# CTRL_Board.net
KiCad netlist of a schematic drawn in Altium Designer
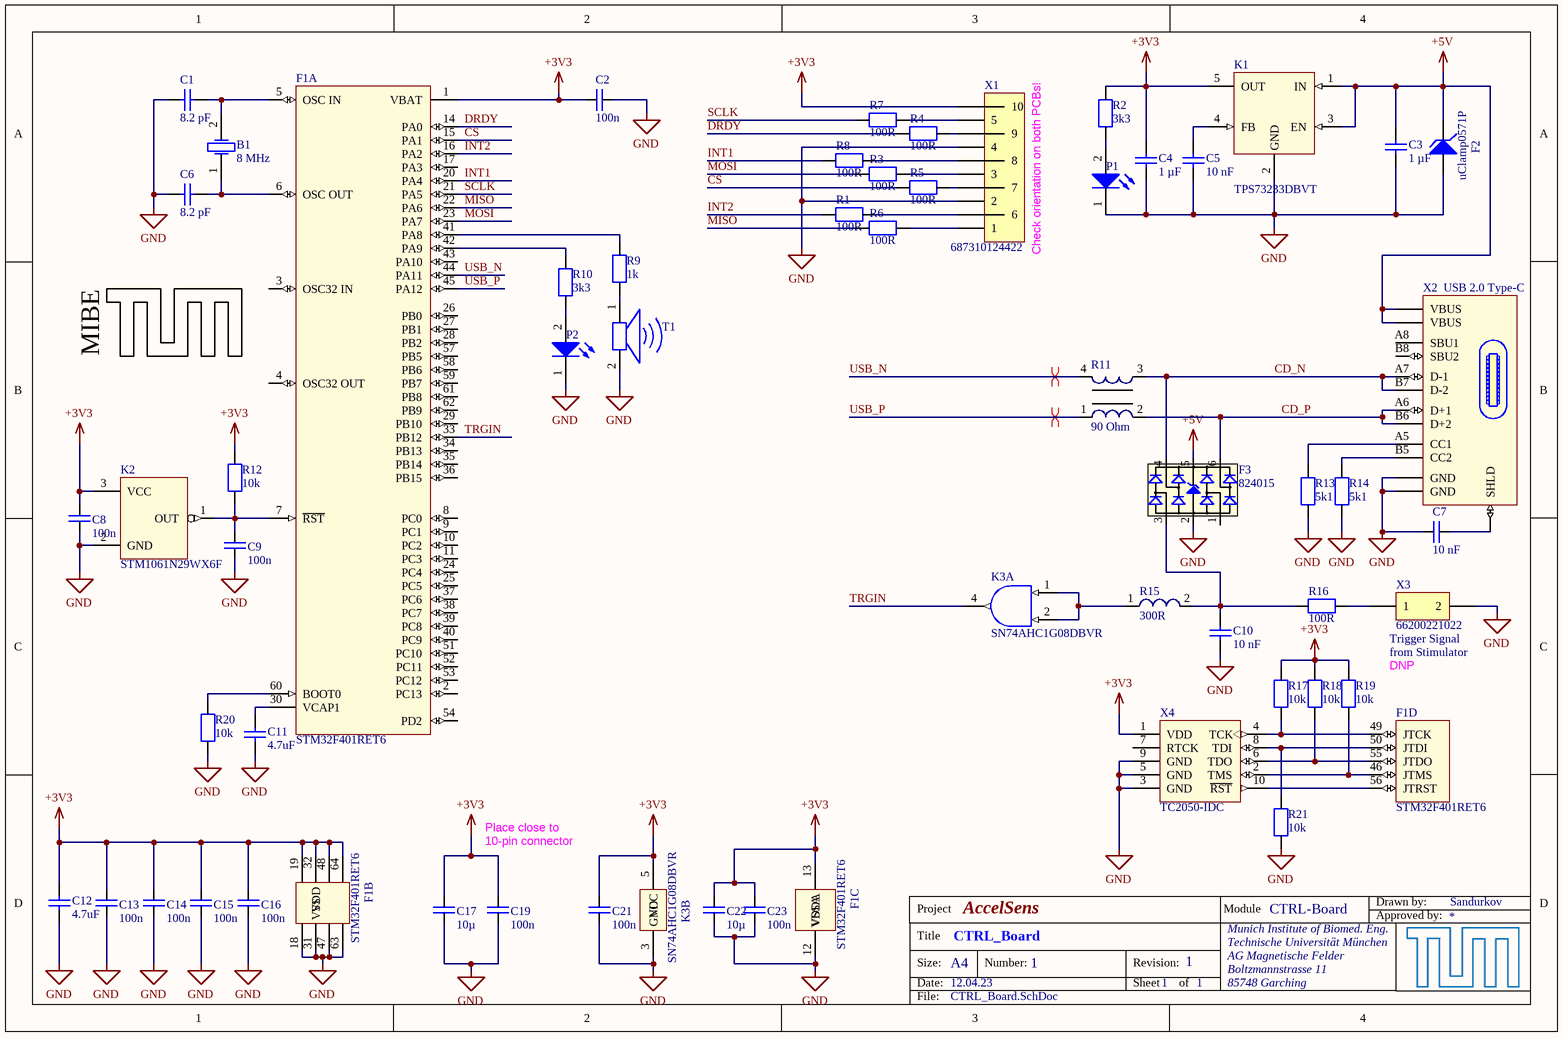
[diagram p0: CTRL_Board.SchDoc]

(export (version "E")
  (design (tool "Eeschema 10.0.6"))
  (components
    (comp (ref "*1")
      (value "TUM & MIBE Logo")
      (footprint "TUM & MIBE Logo")
      (libsource (lib "Mechanical") (part "TUM & MIBE Logo"))
    )
    (comp (ref "B1")
      (value "8 MHz")
      (footprint "DFN190P320X100-2N")
      (description "Crystal, 8 MHz, 8 pF, NX3225GD")
      (libsource (lib "Crystals") (part "NX3225GD-8MHZ-STD-CRA-3"))
    )
    (comp (ref "C1")
      (value "8.2 pF")
      (footprint "CAPC1608X09N")
      (description "8.2 pF, 50 V, 5%, C0G, 0805")
      (libsource (lib "Capacitors") (part "C0603C829C5GACTU"))
    )
    (comp (ref "C2")
      (value "100n")
      (footprint "CAPC1608X08N")
      (description "100n, 0603, X7R, 10%, 50 V")
      (fields (field (name "MANUFACTURER") "Kemet") (field (name "TOLERANCE") "10%"))
      (libsource (lib "Capacitors") (part "C0603C104K5RACTU"))
    )
    (comp (ref "C3")
      (value "1 µF")
      (footprint "CAPC2012X14N")
      (description "1 µF, 25 V, 10%, X7R, 0805")
      (libsource (lib "Capacitors") (part "C0805C105K3RACTU"))
    )
    (comp (ref "C4")
      (value "1 µF")
      (footprint "CAPC2012X14N")
      (description "1 µF, 25 V, 10%, X7R, 0805")
      (libsource (lib "Capacitors") (part "C0805C105K3RACTU"))
    )
    (comp (ref "C5")
      (value "10 nF")
      (footprint "CAPC2012X09N")
      (description "10 nF, 50 V, 10%, X7R, 0805")
      (libsource (lib "Capacitors") (part "C0805C103K5RACTU"))
    )
    (comp (ref "C6")
      (value "8.2 pF")
      (footprint "CAPC1608X09N")
      (description "8.2 pF, 50 V, 5%, C0G, 0805")
      (libsource (lib "Capacitors") (part "C0603C829C5GACTU"))
    )
    (comp (ref "C7")
      (value "10 nF")
      (footprint "0603 (1608x90N), h = 0.9 mm")
      (description "10 nF, 50 V, 10%, X7R, 0603")
      (fields
        (field (name "MANUFACTURER") "Yageo")
        (field (name "MANUFACTURER PART NUMBER") "CC0603KRX7R9BB103")
      )
      (libsource (lib "Capacitors_MIBE") (part "CC0603KRX7R9BB103"))
    )
    (comp (ref "C8")
      (value "100n")
      (footprint "CAPC1608X08N")
      (description "100n, 0603, X7R, 10%, 50 V")
      (fields (field (name "MANUFACTURER") "Kemet") (field (name "TOLERANCE") "10%"))
      (libsource (lib "Capacitors") (part "C0603C104K5RACTU"))
    )
    (comp (ref "C9")
      (value "100n")
      (footprint "CAPC1608X08N")
      (description "100n, 0603, X7R, 10%, 50 V")
      (fields (field (name "MANUFACTURER") "Kemet") (field (name "TOLERANCE") "10%"))
      (libsource (lib "Capacitors") (part "C0603C104K5RACTU"))
    )
    (comp (ref "C10")
      (value "10 nF")
      (footprint "CAPC2012X09N")
      (description "10 nF, 50 V, 10%, X7R, 0805")
      (libsource (lib "Capacitors") (part "C0805C103K5RACTU"))
    )
    (comp (ref "C11")
      (value "4.7uF")
      (footprint "CAPC2012X09N")
      (description "4.7 µF, ± 10%, X5R, 16 V, 0805")
      (libsource (lib "Capacitors") (part "C0805C475K4PACTU"))
    )
    (comp (ref "C12")
      (value "4.7uF")
      (footprint "CAPC2012X09N")
      (description "4.7 µF, ± 10%, X5R, 16 V, 0805")
      (libsource (lib "Capacitors") (part "C0805C475K4PACTU"))
    )
    (comp (ref "C13")
      (value "100n")
      (footprint "CAPC1608X08N")
      (description "100n, 0603, X7R, 10%, 50 V")
      (fields (field (name "MANUFACTURER") "Kemet") (field (name "TOLERANCE") "10%"))
      (libsource (lib "Capacitors") (part "C0603C104K5RACTU"))
    )
    (comp (ref "C14")
      (value "100n")
      (footprint "CAPC1608X08N")
      (description "100n, 0603, X7R, 10%, 50 V")
      (fields (field (name "MANUFACTURER") "Kemet") (field (name "TOLERANCE") "10%"))
      (libsource (lib "Capacitors") (part "C0603C104K5RACTU"))
    )
    (comp (ref "C15")
      (value "100n")
      (footprint "CAPC1608X08N")
      (description "100n, 0603, X7R, 10%, 50 V")
      (fields (field (name "MANUFACTURER") "Kemet") (field (name "TOLERANCE") "10%"))
      (libsource (lib "Capacitors") (part "C0603C104K5RACTU"))
    )
    (comp (ref "C16")
      (value "100n")
      (footprint "CAPC1608X08N")
      (description "100n, 0603, X7R, 10%, 50 V")
      (fields (field (name "MANUFACTURER") "Kemet") (field (name "TOLERANCE") "10%"))
      (libsource (lib "Capacitors") (part "C0603C104K5RACTU"))
    )
    (comp (ref "C17")
      (value "10µ")
      (footprint "CAPC2012X14N")
      (description "10µ, 0805, X5R, 10%, 16 V")
      (fields (field (name "MANUFACTURER") "Kemet") (field (name "TOLERANCE") "10%"))
      (libsource (lib "Capacitors") (part "C0805C106K4PACTU"))
    )
    (comp (ref "C19")
      (value "100n")
      (footprint "CAPC1608X08N")
      (description "100n, 0603, X7R, 10%, 50 V")
      (fields (field (name "MANUFACTURER") "Kemet") (field (name "TOLERANCE") "10%"))
      (libsource (lib "Capacitors") (part "C0603C104K5RACTU"))
    )
    (comp (ref "C21")
      (value "100n")
      (footprint "CAPC1608X08N")
      (description "100n, 0603, X7R, 10%, 50 V")
      (fields (field (name "MANUFACTURER") "Kemet") (field (name "TOLERANCE") "10%"))
      (libsource (lib "Capacitors") (part "C0603C104K5RACTU"))
    )
    (comp (ref "C22")
      (value "10µ")
      (footprint "CAPC2012X14N")
      (description "10µ, 0805, X5R, 10%, 16 V")
      (fields (field (name "MANUFACTURER") "Kemet") (field (name "TOLERANCE") "10%"))
      (libsource (lib "Capacitors") (part "C0805C106K4PACTU"))
    )
    (comp (ref "C23")
      (value "100n")
      (footprint "CAPC1608X08N")
      (description "100n, 0603, X7R, 10%, 50 V")
      (fields (field (name "MANUFACTURER") "Kemet") (field (name "TOLERANCE") "10%"))
      (libsource (lib "Capacitors") (part "C0603C104K5RACTU"))
    )
    (comp (ref "F1")
      (value "STM32F401RET6")
      (footprint "LQFP-64")
      (description "M4, 512 kB, 84 MHz")
      (fields (field (name "MANUFACTURER") "STMicroelectronics"))
      (libsource (lib "Microcontroller_MIBE") (part "STM32F401RET6"))
    )
    (comp (ref "F2")
      (value "uClamp0571P")
      (footprint "DFN110P160X55-2N")
      (description "TVS DIODE 5V 15V SGP1610N2")
      (fields
        (field (name "MANUFACTURER") "Semtech")
        (field (name "MANUFACTURER PART NUMBER") "UCLAMP0571P.TNT")
      )
      (libsource (lib "Diodes") (part "UCLAMP0571P.TNT"))
    )
    (comp (ref "F3")
      (value "824015")
      (footprint "SOT23_6L")
      (description "TVS Diode WE-TVS-HS, VRWM=5V")
      (fields
        (field (name "MANUFACTURER") "Würth Elektronik eiSos GmbH")
        (field (name "CREATED BY") "Christin Zierenner")
      )
      (libsource (lib "Diodes") (part "WE-TVS-HS, 824015"))
    )
    (comp (ref "K1")
      (value "TPS73233DBVT")
      (footprint "SOT95P280X145-5N")
      (description "Low Noise, Positive Output LDO, 250 mA, 3.3V")
      (fields (field (name "PUBLISHER") "Stephan Huber"))
      (libsource (lib "Regulators") (part "TPS73233DBVT"))
    )
    (comp (ref "K2")
      (value "STM1061N29WX6F")
      (footprint "SOT95P237X112-3N")
      (description "Low Power Voltage Detector, Open Drain, 2,9 V Threshold, SOT23-3")
      (libsource (lib "Supervisors") (part "STM1061N29WX6F"))
    )
    (comp (ref "K3")
      (value "SN74AHC1G08DBVR")
      (footprint "SOT95P280X145-5N")
      (description "CMOS Single AND-Gate, AHC, 2 V - 5.5 V, 8 mA, Ultra High Speed")
      (libsource (lib "Logic") (part "SN74AHC1G08DBVR"))
    )
    (comp (ref "P1")
      (value "green")
      (footprint "WL-SMCW_0603")
      (description "WL-SMCW LED, green, 30 mA, 2 V, 570 nmr, 0603, Bright Green,  140°")
      (fields (field (name "PART NUMBER") "150060VS75000") (field (name "PUBLISHER") "Wurth Elektronik"))
      (libsource (lib "Opto") (part "150060VS75000"))
    )
    (comp (ref "P2")
      (value "green")
      (footprint "WL-SMCW_0603")
      (description "WL-SMCW LED, green, 30 mA, 2 V, 570 nmr, 0603, Bright Green,  140°")
      (fields (field (name "PART NUMBER") "150060VS75000") (field (name "PUBLISHER") "Wurth Elektronik"))
      (libsource (lib "Opto") (part "150060VS75000"))
    )
    (comp (ref "R1")
      (value "100R")
      (footprint "RESC1608X05N")
      (description "100R, 0603, 0.25 W, 1%, 75 V, pulse proof")
      (fields (field (name "TOLERANCE") "1%") (field (name "MANUFACTURER") "Vishay"))
      (libsource (lib "Resistors") (part "CRCW0603100RFKEAHP"))
    )
    (comp (ref "R2")
      (value "3k3")
      (footprint "RESC1608X05N")
      (description "3k3, 0603, 0.1 W, 1%, 75 V")
      (fields (field (name "TOLERANCE") "1%") (field (name "MANUFACTURER") "Vishay"))
      (libsource (lib "") (part "CRCW06033K30FKEA_1"))
    )
    (comp (ref "R3")
      (value "100R")
      (footprint "RESC1608X05N")
      (description "100R, 0603, 0.25 W, 1%, 75 V, pulse proof")
      (fields (field (name "TOLERANCE") "1%") (field (name "MANUFACTURER") "Vishay"))
      (libsource (lib "Resistors") (part "CRCW0603100RFKEAHP"))
    )
    (comp (ref "R4")
      (value "100R")
      (footprint "RESC1608X05N")
      (description "100R, 0603, 0.25 W, 1%, 75 V, pulse proof")
      (fields (field (name "TOLERANCE") "1%") (field (name "MANUFACTURER") "Vishay"))
      (libsource (lib "Resistors") (part "CRCW0603100RFKEAHP"))
    )
    (comp (ref "R5")
      (value "100R")
      (footprint "RESC1608X05N")
      (description "100R, 0603, 0.25 W, 1%, 75 V, pulse proof")
      (fields (field (name "TOLERANCE") "1%") (field (name "MANUFACTURER") "Vishay"))
      (libsource (lib "Resistors") (part "CRCW0603100RFKEAHP"))
    )
    (comp (ref "R6")
      (value "100R")
      (footprint "RESC1608X05N")
      (description "100R, 0603, 0.25 W, 1%, 75 V, pulse proof")
      (fields (field (name "TOLERANCE") "1%") (field (name "MANUFACTURER") "Vishay"))
      (libsource (lib "Resistors") (part "CRCW0603100RFKEAHP"))
    )
    (comp (ref "R7")
      (value "100R")
      (footprint "RESC1608X05N")
      (description "100R, 0603, 0.25 W, 1%, 75 V, pulse proof")
      (fields (field (name "TOLERANCE") "1%") (field (name "MANUFACTURER") "Vishay"))
      (libsource (lib "Resistors") (part "CRCW0603100RFKEAHP"))
    )
    (comp (ref "R8")
      (value "100R")
      (footprint "RESC1608X05N")
      (description "100R, 0603, 0.25 W, 1%, 75 V, pulse proof")
      (fields (field (name "TOLERANCE") "1%") (field (name "MANUFACTURER") "Vishay"))
      (libsource (lib "Resistors") (part "CRCW0603100RFKEAHP"))
    )
    (comp (ref "R9")
      (value "1k")
      (footprint "RESC1608X05N")
      (description "1k, 0603, 0.1 W, 1%, 75 V")
      (fields (field (name "TOLERANCE") "1%") (field (name "MANUFACTURER") "Vishay"))
      (libsource (lib "Resistors") (part "CRCW06031K00FKEA"))
    )
    (comp (ref "R10")
      (value "3k3")
      (footprint "RESC1608X05N")
      (description "3k3, 0603, 0.1 W, 1%, 75 V")
      (fields (field (name "TOLERANCE") "1%") (field (name "MANUFACTURER") "Vishay"))
      (libsource (lib "Resistors") (part "CRCW06033K30FKEA"))
    )
    (comp (ref "R11")
      (value "90 Ohm")
      (footprint "WE-CNSW, 1206")
      (description "SMD Common Mode Noise Suppressor WE-CNSW,  Z= 90 Ohm")
      (fields
        (field (name "PARTNO") "744232090")
        (field (name "MANUFACTURER") "Würth Elektronik eiSos GmbH")
        (field (name "CREATED BY") "Christin Zierenner")
      )
      (libsource (lib "Inductors") (part "WE-CNSW 1206, 744232090"))
    )
    (comp (ref "R12")
      (value "10k")
      (footprint "RESC1608X05N")
      (description "10k, 0603, 0.1 W, 1%, 75 V")
      (fields (field (name "TOLERANCE") "1%") (field (name "MANUFACTURER") "Vishay"))
      (libsource (lib "Resistors") (part "CRCW060310K0FKEA"))
    )
    (comp (ref "R13")
      (value "5k1")
      (footprint "RES0603")
      (description "5k1, 0.1 W, 1%, 75 V, 0603")
      (fields
        (field (name "MANUFACTURER") "Vishay")
        (field (name "MANUFACTURER PART NUMBER") "CRCW06035K10FKEA")
      )
      (libsource (lib "Resistors_MIBE") (part "CRCW06035K10FKEA"))
    )
    (comp (ref "R14")
      (value "5k1")
      (footprint "RES0603")
      (description "5k1, 0.1 W, 1%, 75 V, 0603")
      (fields
        (field (name "MANUFACTURER") "Vishay")
        (field (name "MANUFACTURER PART NUMBER") "CRCW06035K10FKEA")
      )
      (libsource (lib "Resistors_MIBE") (part "CRCW06035K10FKEA"))
    )
    (comp (ref "R15")
      (value "300R")
      (footprint "0603 (WE-CBF)")
      (description "300R / 100 MHz, 2 A, 0R15, WE-CBF")
      (fields
        (field (name "MANUFACTURER") "Wurth Electronics")
        (field (name "MANUFACTURER PART NUMBER") "742792641")
      )
      (libsource (lib "Inductors_MIBE") (part "742792641"))
    )
    (comp (ref "R16")
      (value "100R")
      (footprint "RESC1608X05N")
      (description "100R, 0603, 0.25 W, 1%, 75 V, pulse proof")
      (fields (field (name "TOLERANCE") "1%") (field (name "MANUFACTURER") "Vishay"))
      (libsource (lib "") (part "CRCW0603100RFKEAHP_1"))
    )
    (comp (ref "R17")
      (value "10k")
      (footprint "RESC1608X05N")
      (description "10k, 0603, 0.1 W, 0.1%, 75 V")
      (fields (field (name "TOLERANCE") "0.1%") (field (name "MANUFACTURER") "Panasonic"))
      (libsource (lib "Resistors") (part "ERA3AEB103V"))
    )
    (comp (ref "R18")
      (value "10k")
      (footprint "RESC1608X05N")
      (description "10k, 0603, 0.1 W, 0.1%, 75 V")
      (fields (field (name "TOLERANCE") "0.1%") (field (name "MANUFACTURER") "Panasonic"))
      (libsource (lib "Resistors") (part "ERA3AEB103V"))
    )
    (comp (ref "R19")
      (value "10k")
      (footprint "RESC1608X05N")
      (description "10k, 0603, 0.1 W, 0.1%, 75 V")
      (fields (field (name "TOLERANCE") "0.1%") (field (name "MANUFACTURER") "Panasonic"))
      (libsource (lib "Resistors") (part "ERA3AEB103V"))
    )
    (comp (ref "R20")
      (value "10k")
      (footprint "RESC1608X05N")
      (description "10k, 0603, 0.1 W, 1%, 75 V")
      (fields (field (name "TOLERANCE") "1%") (field (name "MANUFACTURER") "Vishay"))
      (libsource (lib "Resistors") (part "CRCW060310K0FKEA"))
    )
    (comp (ref "R21")
      (value "10k")
      (footprint "RESC1608X05N")
      (description "10k, 0603, 0.1 W, 0.1%, 75 V")
      (fields (field (name "TOLERANCE") "0.1%") (field (name "MANUFACTURER") "Panasonic"))
      (libsource (lib "Resistors") (part "ERA3AEB103V"))
    )
    (comp (ref "T1")
      (value "Summer")
      (footprint "PKLCS1212E4001-R1")
      (description "SUMMER, SMD, 4KHZ EXTERN BESCHALTEN")
      (libsource (lib "Electromechanical") (part "PKLCS1212E4001-R1"))
    )
    (comp (ref "X1")
      (value "687310124422")
      (footprint "687310124422")
      (description "Ffc / Fpc Board Connector, Vertical, Surface Mount, Receptacle, 10, 0.5 Mm Rohs Compliant: Yes")
      (fields (field (name "MANUFACTURER") "Wurth Electronics"))
      (libsource (lib "Connectors_MIBE") (part "687310124422"))
    )
    (comp (ref "X2")
      (value "USB 2.0 Type-C")
      (footprint "629722000214")
      (description "USB 2.0 Type C")
      (fields
        (field (name "MANUFACTURER") "Wurth Electronics")
        (field (name "MANUFACTURER PART NUMBER") "629722000214")
      )
      (libsource (lib "Connectors_MIBE") (part "629722000214"))
    )
    (comp (ref "X3")
      (value "66200221022")
      (footprint "66200221022")
      (description "WR-MPC3 3.00 mm Male Dual Row Angled Header with Plastic Pegs")
      (fields
        (field (name "MANUFACTURER") "Würth Elektronik eiSos GmbH")
        (field (name "CREATED BY") "Karrer Zheng")
      )
      (libsource (lib "Connectors") (part "WE-3.00 mm Micro Power Connector 66200221022"))
    )
    (comp (ref "X4")
      (value "TC2050-IDC")
      (footprint "TC2050-IDC")
      (description "JTAG - Adapter Cbl Plug Of Nails 10PIN")
      (fields (field (name "MANUFACTURER") "Tag-Connect"))
      (libsource (lib "Connectors_MIBE") (part "TC2050-IDC"))
    )
  )
  (nets
    (net (code "1") (name "+3V3") (class "Default")
      (node (ref "C12") (pin "1") (pinfunction "1_1") (pintype "passive"))
      (node (ref "C13") (pin "1") (pinfunction "1_1") (pintype "passive"))
      (node (ref "C14") (pin "1") (pinfunction "1_1") (pintype "passive"))
      (node (ref "C15") (pin "1") (pinfunction "1_1") (pintype "passive"))
      (node (ref "C16") (pin "1") (pinfunction "1_1") (pintype "passive"))
      (node (ref "C17") (pin "1") (pinfunction "1_1") (pintype "passive"))
      (node (ref "C19") (pin "1") (pinfunction "1_1") (pintype "passive"))
      (node (ref "C2") (pin "1") (pinfunction "1_1") (pintype "passive"))
      (node (ref "C21") (pin "1") (pinfunction "1_1") (pintype "passive"))
      (node (ref "C22") (pin "1") (pinfunction "1_1") (pintype "passive"))
      (node (ref "C23") (pin "1") (pinfunction "1_1") (pintype "passive"))
      (node (ref "C4") (pin "1") (pinfunction "1_1") (pintype "passive"))
      (node (ref "C8") (pin "1") (pinfunction "1_1") (pintype "passive"))
      (node (ref "F1") (pin "1") (pinfunction "VBAT_1") (pintype "power_in"))
      (node (ref "F1") (pin "13") (pinfunction "VDDA_13") (pintype "power_in"))
      (node (ref "F1") (pin "19") (pinfunction "VDD_19") (pintype "power_in"))
      (node (ref "F1") (pin "32") (pinfunction "VDD_32") (pintype "power_in"))
      (node (ref "F1") (pin "48") (pinfunction "VDD_48") (pintype "power_in"))
      (node (ref "F1") (pin "64") (pinfunction "VDD_64") (pintype "power_in"))
      (node (ref "K1") (pin "5") (pinfunction "OUT_5") (pintype "power_in"))
      (node (ref "K2") (pin "3") (pinfunction "VCC_3") (pintype "power_in"))
      (node (ref "K3") (pin "5") (pinfunction "VCC_5") (pintype "power_in"))
      (node (ref "R12") (pin "1") (pinfunction "1_1") (pintype "passive"))
      (node (ref "R17") (pin "1") (pinfunction "1_1") (pintype "passive"))
      (node (ref "R18") (pin "1") (pinfunction "1_1") (pintype "passive"))
      (node (ref "R19") (pin "1") (pinfunction "1_1") (pintype "passive"))
      (node (ref "R2") (pin "1") (pinfunction "1_1") (pintype "passive"))
      (node (ref "X1") (pin "10") (pinfunction "10_10") (pintype "passive"))
      (node (ref "X4") (pin "1") (pinfunction "VDD_1") (pintype "power_in"))
    )
    (net (code "2") (name "+5V") (class "Default")
      (node (ref "C3") (pin "1") (pinfunction "1_1") (pintype "passive"))
      (node (ref "F2") (pin "1") (pinfunction "C_1") (pintype "passive"))
      (node (ref "F3") (pin "5") (pinfunction "VDD_5") (pintype "passive"))
      (node (ref "K1") (pin "1") (pinfunction "IN_1") (pintype "input"))
      (node (ref "K1") (pin "3") (pinfunction "EN_3") (pintype "input"))
      (node (ref "X2") (pin "VBUS") (pinfunction "VBUS_VBUS") (pintype "power_in"))
    )
    (net (code "3") (name "/CD_N") (class "Default")
      (node (ref "F3") (pin "4") (pinfunction "I/O3_4") (pintype "passive"))
      (node (ref "R11") (pin "3") (pinfunction "3_3") (pintype "passive"))
      (node (ref "X2") (pin "A7") (pinfunction "D-1_A7") (pintype "bidirectional"))
      (node (ref "X2") (pin "B7") (pinfunction "D-2_B7") (pintype "passive"))
    )
    (net (code "4") (name "/CD_P") (class "Default")
      (node (ref "F3") (pin "6") (pinfunction "I/O4_6") (pintype "passive"))
      (node (ref "R11") (pin "2") (pinfunction "2_2") (pintype "passive"))
      (node (ref "X2") (pin "A6") (pinfunction "D+1_A6") (pintype "bidirectional"))
      (node (ref "X2") (pin "B6") (pinfunction "D+2_B6") (pintype "power_in"))
    )
    (net (code "5") (name "/CS") (class "Default")
      (node (ref "F1") (pin "15") (pinfunction "PA1_15") (pintype "bidirectional"))
      (node (ref "R5") (pin "2") (pinfunction "2_2") (pintype "passive"))
    )
    (net (code "6") (name "/DRDY") (class "Default")
      (node (ref "F1") (pin "14") (pinfunction "PA0_14") (pintype "bidirectional"))
      (node (ref "R4") (pin "2") (pinfunction "2_2") (pintype "passive"))
    )
    (net (code "7") (name "/INT1") (class "Default")
      (node (ref "F1") (pin "20") (pinfunction "PA4_20") (pintype "bidirectional"))
      (node (ref "R8") (pin "2") (pinfunction "2_2") (pintype "passive"))
    )
    (net (code "8") (name "/INT2") (class "Default")
      (node (ref "F1") (pin "16") (pinfunction "PA2_16") (pintype "bidirectional"))
      (node (ref "R1") (pin "2") (pinfunction "2_2") (pintype "passive"))
    )
    (net (code "9") (name "/MISO") (class "Default")
      (node (ref "F1") (pin "22") (pinfunction "PA6_22") (pintype "bidirectional"))
      (node (ref "R6") (pin "2") (pinfunction "2_2") (pintype "passive"))
    )
    (net (code "10") (name "/MOSI") (class "Default")
      (node (ref "F1") (pin "23") (pinfunction "PA7_23") (pintype "bidirectional"))
      (node (ref "R3") (pin "2") (pinfunction "2_2") (pintype "passive"))
    )
    (net (code "11") (name "/SCLK") (class "Default")
      (node (ref "F1") (pin "21") (pinfunction "PA5_21") (pintype "bidirectional"))
      (node (ref "R7") (pin "2") (pinfunction "2_2") (pintype "passive"))
    )
    (net (code "12") (name "/TRGIN") (class "Default")
      (node (ref "F1") (pin "33") (pinfunction "PB12_33") (pintype "bidirectional"))
      (node (ref "K3") (pin "4") (pinfunction "Y_4") (pintype "output"))
    )
    (net (code "13") (name "/USB_N") (class "Default")
      (node (ref "F1") (pin "44") (pinfunction "PA11_44") (pintype "bidirectional"))
      (node (ref "R11") (pin "4") (pinfunction "4_4") (pintype "passive"))
    )
    (net (code "14") (name "/USB_P") (class "Default")
      (node (ref "F1") (pin "45") (pinfunction "PA12_45") (pintype "bidirectional"))
      (node (ref "R11") (pin "1") (pinfunction "1_1") (pintype "passive"))
    )
    (net (code "15") (name "GND") (class "Default")
      (node (ref "C1") (pin "1") (pinfunction "1_1") (pintype "passive"))
      (node (ref "C10") (pin "2") (pinfunction "2_2") (pintype "passive"))
      (node (ref "C11") (pin "2") (pinfunction "2_2") (pintype "passive"))
      (node (ref "C12") (pin "2") (pinfunction "2_2") (pintype "passive"))
      (node (ref "C13") (pin "2") (pinfunction "2_2") (pintype "passive"))
      (node (ref "C14") (pin "2") (pinfunction "2_2") (pintype "passive"))
      (node (ref "C15") (pin "2") (pinfunction "2_2") (pintype "passive"))
      (node (ref "C16") (pin "2") (pinfunction "2_2") (pintype "passive"))
      (node (ref "C17") (pin "2") (pinfunction "2_2") (pintype "passive"))
      (node (ref "C19") (pin "2") (pinfunction "2_2") (pintype "passive"))
      (node (ref "C2") (pin "2") (pinfunction "2_2") (pintype "passive"))
      (node (ref "C21") (pin "2") (pinfunction "2_2") (pintype "passive"))
      (node (ref "C22") (pin "2") (pinfunction "2_2") (pintype "passive"))
      (node (ref "C23") (pin "2") (pinfunction "2_2") (pintype "passive"))
      (node (ref "C3") (pin "2") (pinfunction "2_2") (pintype "passive"))
      (node (ref "C4") (pin "2") (pinfunction "2_2") (pintype "passive"))
      (node (ref "C5") (pin "2") (pinfunction "2_2") (pintype "passive"))
      (node (ref "C6") (pin "1") (pinfunction "1_1") (pintype "passive"))
      (node (ref "C7") (pin "1") (pinfunction "1_1") (pintype "passive"))
      (node (ref "C8") (pin "2") (pinfunction "2_2") (pintype "passive"))
      (node (ref "C9") (pin "2") (pinfunction "2_2") (pintype "passive"))
      (node (ref "F1") (pin "12") (pinfunction "VSSA_12") (pintype "power_in"))
      (node (ref "F1") (pin "18") (pinfunction "VSS_18") (pintype "power_in"))
      (node (ref "F1") (pin "31") (pinfunction "VSS_31") (pintype "power_in"))
      (node (ref "F1") (pin "47") (pinfunction "VSS_47") (pintype "power_in"))
      (node (ref "F1") (pin "63") (pinfunction "VSS_63") (pintype "power_in"))
      (node (ref "F2") (pin "2") (pinfunction "A_2") (pintype "passive"))
      (node (ref "F3") (pin "2") (pinfunction "GND_2") (pintype "passive"))
      (node (ref "K1") (pin "2") (pinfunction "GND_2") (pintype "power_in"))
      (node (ref "K2") (pin "2") (pinfunction "GND_2") (pintype "power_in"))
      (node (ref "K3") (pin "3") (pinfunction "GND_3") (pintype "power_in"))
      (node (ref "P1") (pin "1") (pinfunction "K_1") (pintype "passive"))
      (node (ref "P2") (pin "1") (pinfunction "K_1") (pintype "passive"))
      (node (ref "R13") (pin "2") (pinfunction "2_2") (pintype "passive"))
      (node (ref "R14") (pin "2") (pinfunction "2_2") (pintype "passive"))
      (node (ref "R20") (pin "2") (pinfunction "2_2") (pintype "passive"))
      (node (ref "R21") (pin "2") (pinfunction "2_2") (pintype "passive"))
      (node (ref "T1") (pin "2") (pinfunction "2_2") (pintype "passive"))
      (node (ref "X1") (pin "2") (pinfunction "2_2") (pintype "passive"))
      (node (ref "X1") (pin "4") (pinfunction "4_4") (pintype "passive"))
      (node (ref "X2") (pin "GND") (pinfunction "GND_GND") (pintype "power_in"))
      (node (ref "X3") (pin "2") (pinfunction "2_2") (pintype "passive"))
      (node (ref "X4") (pin "3") (pinfunction "GND_3") (pintype "power_in"))
      (node (ref "X4") (pin "5") (pinfunction "GND_5") (pintype "power_in"))
      (node (ref "X4") (pin "9") (pinfunction "GND_9") (pintype "power_in"))
    )
    (net (code "16") (name "Net-(F1A-BOOT0)") (class "Default")
      (node (ref "F1") (pin "60") (pinfunction "BOOT0_60") (pintype "input"))
      (node (ref "R20") (pin "1") (pinfunction "1_1") (pintype "passive"))
    )
    (net (code "17") (name "Net-(F1A-OSC_IN)") (class "Default")
      (node (ref "B1") (pin "2") (pinfunction "2_2") (pintype "passive"))
      (node (ref "C1") (pin "2") (pinfunction "2_2") (pintype "passive"))
      (node (ref "F1") (pin "5") (pinfunction "OSC_IN_5") (pintype "bidirectional"))
    )
    (net (code "18") (name "Net-(F1A-OSC_OUT)") (class "Default")
      (node (ref "B1") (pin "1") (pinfunction "1_1") (pintype "passive"))
      (node (ref "C6") (pin "2") (pinfunction "2_2") (pintype "passive"))
      (node (ref "F1") (pin "6") (pinfunction "OSC_OUT_6") (pintype "bidirectional"))
    )
    (net (code "19") (name "Net-(F1A-PA8)") (class "Default")
      (node (ref "F1") (pin "41") (pinfunction "PA8_41") (pintype "bidirectional"))
      (node (ref "R9") (pin "1") (pinfunction "1_1") (pintype "passive"))
    )
    (net (code "20") (name "Net-(F1A-PA9)") (class "Default")
      (node (ref "F1") (pin "42") (pinfunction "PA9_42") (pintype "bidirectional"))
      (node (ref "R10") (pin "2") (pinfunction "2_2") (pintype "passive"))
    )
    (net (code "21") (name "Net-(F1A-VCAP1)") (class "Default")
      (node (ref "C11") (pin "1") (pinfunction "1_1") (pintype "passive"))
      (node (ref "F1") (pin "30") (pinfunction "VCAP1_30") (pintype "power_in"))
    )
    (net (code "22") (name "Net-(F1A-~{RST})") (class "Default")
      (node (ref "C9") (pin "1") (pinfunction "1_1") (pintype "passive"))
      (node (ref "F1") (pin "7") (pinfunction "~{RST}_7") (pintype "input"))
      (node (ref "K2") (pin "1") (pinfunction "OUT_1") (pintype "output"))
      (node (ref "R12") (pin "2") (pinfunction "2_2") (pintype "passive"))
    )
    (net (code "23") (name "Net-(F1D-JTCK)") (class "Default")
      (node (ref "F1") (pin "49") (pinfunction "JTCK_49") (pintype "bidirectional"))
      (node (ref "R17") (pin "2") (pinfunction "2_2") (pintype "passive"))
      (node (ref "X4") (pin "4") (pinfunction "TCK_4") (pintype "output"))
    )
    (net (code "24") (name "Net-(F1D-JTDI)") (class "Default")
      (node (ref "F1") (pin "50") (pinfunction "JTDI_50") (pintype "bidirectional"))
      (node (ref "R21") (pin "1") (pinfunction "1_1") (pintype "passive"))
      (node (ref "X4") (pin "8") (pinfunction "TDI_8") (pintype "bidirectional"))
    )
    (net (code "25") (name "Net-(F1D-JTDO)") (class "Default")
      (node (ref "F1") (pin "55") (pinfunction "JTDO_55") (pintype "bidirectional"))
      (node (ref "R18") (pin "2") (pinfunction "2_2") (pintype "passive"))
      (node (ref "X4") (pin "6") (pinfunction "TDO_6") (pintype "bidirectional"))
    )
    (net (code "26") (name "Net-(F1D-JTMS)") (class "Default")
      (node (ref "F1") (pin "46") (pinfunction "JTMS_46") (pintype "bidirectional"))
      (node (ref "R19") (pin "2") (pinfunction "2_2") (pintype "passive"))
      (node (ref "X4") (pin "2") (pinfunction "TMS_2") (pintype "bidirectional"))
    )
    (net (code "27") (name "Net-(F1D-JTRST)") (class "Default")
      (node (ref "F1") (pin "56") (pinfunction "JTRST_56") (pintype "bidirectional"))
      (node (ref "X4") (pin "10") (pinfunction "~{RST}_10") (pintype "output"))
    )
    (net (code "28") (name "Net-(F3-I{slash}O2)") (class "Default")
      (node (ref "C10") (pin "1") (pinfunction "1_1") (pintype "passive"))
      (node (ref "F3") (pin "3") (pinfunction "I/O2_3") (pintype "passive"))
      (node (ref "R15") (pin "2") (pinfunction "2_2") (pintype "passive"))
      (node (ref "R16") (pin "1") (pinfunction "1_1") (pintype "passive"))
    )
    (net (code "29") (name "Net-(K1-FB)") (class "Default")
      (node (ref "C5") (pin "1") (pinfunction "1_1") (pintype "passive"))
      (node (ref "K1") (pin "4") (pinfunction "FB_4") (pintype "input"))
    )
    (net (code "30") (name "Net-(K3A-A)") (class "Default")
      (node (ref "K3") (pin "1") (pinfunction "A_1") (pintype "input"))
      (node (ref "K3") (pin "2") (pinfunction "B_2") (pintype "input"))
      (node (ref "R15") (pin "1") (pinfunction "1_1") (pintype "passive"))
    )
    (net (code "31") (name "Net-(P1-A)") (class "Default")
      (node (ref "P1") (pin "2") (pinfunction "A_2") (pintype "passive"))
      (node (ref "R2") (pin "2") (pinfunction "2_2") (pintype "passive"))
    )
    (net (code "32") (name "Net-(P2-A)") (class "Default")
      (node (ref "P2") (pin "2") (pinfunction "A_2") (pintype "passive"))
      (node (ref "R10") (pin "1") (pinfunction "1_1") (pintype "passive"))
    )
    (net (code "33") (name "Net-(R1-Pad1)") (class "Default")
      (node (ref "R1") (pin "1") (pinfunction "1_1") (pintype "passive"))
      (node (ref "X1") (pin "6") (pinfunction "6_6") (pintype "passive"))
    )
    (net (code "34") (name "Net-(R3-Pad1)") (class "Default")
      (node (ref "R3") (pin "1") (pinfunction "1_1") (pintype "passive"))
      (node (ref "X1") (pin "3") (pinfunction "3_3") (pintype "passive"))
    )
    (net (code "35") (name "Net-(R4-Pad1)") (class "Default")
      (node (ref "R4") (pin "1") (pinfunction "1_1") (pintype "passive"))
      (node (ref "X1") (pin "9") (pinfunction "9_9") (pintype "passive"))
    )
    (net (code "36") (name "Net-(R5-Pad1)") (class "Default")
      (node (ref "R5") (pin "1") (pinfunction "1_1") (pintype "passive"))
      (node (ref "X1") (pin "7") (pinfunction "7_7") (pintype "passive"))
    )
    (net (code "37") (name "Net-(R6-Pad1)") (class "Default")
      (node (ref "R6") (pin "1") (pinfunction "1_1") (pintype "passive"))
      (node (ref "X1") (pin "1") (pinfunction "1_1") (pintype "passive"))
    )
    (net (code "38") (name "Net-(R7-Pad1)") (class "Default")
      (node (ref "R7") (pin "1") (pinfunction "1_1") (pintype "passive"))
      (node (ref "X1") (pin "5") (pinfunction "5_5") (pintype "passive"))
    )
    (net (code "39") (name "Net-(R8-Pad1)") (class "Default")
      (node (ref "R8") (pin "1") (pinfunction "1_1") (pintype "passive"))
      (node (ref "X1") (pin "8") (pinfunction "8_8") (pintype "passive"))
    )
    (net (code "40") (name "Net-(R9-Pad2)") (class "Default")
      (node (ref "R9") (pin "2") (pinfunction "2_2") (pintype "passive"))
      (node (ref "T1") (pin "1") (pinfunction "1_1") (pintype "passive"))
    )
    (net (code "41") (name "Net-(R16-Pad2)") (class "Default")
      (node (ref "R16") (pin "2") (pinfunction "2_2") (pintype "passive"))
      (node (ref "X3") (pin "1") (pinfunction "1_1") (pintype "passive"))
    )
    (net (code "42") (name "Net-(X2-CC1)") (class "Default")
      (node (ref "R13") (pin "1") (pinfunction "1_1") (pintype "passive"))
      (node (ref "X2") (pin "A5") (pinfunction "CC1_A5") (pintype "passive"))
    )
    (net (code "43") (name "Net-(X2-CC2)") (class "Default")
      (node (ref "R14") (pin "1") (pinfunction "1_1") (pintype "passive"))
      (node (ref "X2") (pin "B5") (pinfunction "CC2_B5") (pintype "power_in"))
    )
    (net (code "44") (name "Net-(X2-SHLD)") (class "Default")
      (node (ref "C7") (pin "2") (pinfunction "2_2") (pintype "passive"))
      (node (ref "X2") (pin "1") (pinfunction "SHLD_1") (pintype "bidirectional"))
    )
    (net (code "45") (name "unconnected-(F1A-OSC32_IN-Pad3)") (class "Default")
      (node (ref "F1") (pin "3") (pinfunction "OSC32_IN_3") (pintype "bidirectional"))
    )
    (net (code "46") (name "unconnected-(F1A-OSC32_OUT-Pad4)") (class "Default")
      (node (ref "F1") (pin "4") (pinfunction "OSC32_OUT_4") (pintype "bidirectional"))
    )
    (net (code "47") (name "unconnected-(F1A-PA3-Pad17)") (class "Default")
      (node (ref "F1") (pin "17") (pinfunction "PA3_17") (pintype "bidirectional"))
    )
    (net (code "48") (name "unconnected-(F1A-PA10-Pad43)") (class "Default")
      (node (ref "F1") (pin "43") (pinfunction "PA10_43") (pintype "bidirectional"))
    )
    (net (code "49") (name "unconnected-(F1A-PB0-Pad26)") (class "Default")
      (node (ref "F1") (pin "26") (pinfunction "PB0_26") (pintype "bidirectional"))
    )
    (net (code "50") (name "unconnected-(F1A-PB1-Pad27)") (class "Default")
      (node (ref "F1") (pin "27") (pinfunction "PB1_27") (pintype "bidirectional"))
    )
    (net (code "51") (name "unconnected-(F1A-PB2-Pad28)") (class "Default")
      (node (ref "F1") (pin "28") (pinfunction "PB2_28") (pintype "bidirectional"))
    )
    (net (code "52") (name "unconnected-(F1A-PB5-Pad57)") (class "Default")
      (node (ref "F1") (pin "57") (pinfunction "PB5_57") (pintype "bidirectional"))
    )
    (net (code "53") (name "unconnected-(F1A-PB6-Pad58)") (class "Default")
      (node (ref "F1") (pin "58") (pinfunction "PB6_58") (pintype "bidirectional"))
    )
    (net (code "54") (name "unconnected-(F1A-PB7-Pad59)") (class "Default")
      (node (ref "F1") (pin "59") (pinfunction "PB7_59") (pintype "bidirectional"))
    )
    (net (code "55") (name "unconnected-(F1A-PB8-Pad61)") (class "Default")
      (node (ref "F1") (pin "61") (pinfunction "PB8_61") (pintype "bidirectional"))
    )
    (net (code "56") (name "unconnected-(F1A-PB9-Pad62)") (class "Default")
      (node (ref "F1") (pin "62") (pinfunction "PB9_62") (pintype "bidirectional"))
    )
    (net (code "57") (name "unconnected-(F1A-PB10-Pad29)") (class "Default")
      (node (ref "F1") (pin "29") (pinfunction "PB10_29") (pintype "bidirectional"))
    )
    (net (code "58") (name "unconnected-(F1A-PB13-Pad34)") (class "Default")
      (node (ref "F1") (pin "34") (pinfunction "PB13_34") (pintype "bidirectional"))
    )
    (net (code "59") (name "unconnected-(F1A-PB14-Pad35)") (class "Default")
      (node (ref "F1") (pin "35") (pinfunction "PB14_35") (pintype "bidirectional"))
    )
    (net (code "60") (name "unconnected-(F1A-PB15-Pad36)") (class "Default")
      (node (ref "F1") (pin "36") (pinfunction "PB15_36") (pintype "bidirectional"))
    )
    (net (code "61") (name "unconnected-(F1A-PC0-Pad8)") (class "Default")
      (node (ref "F1") (pin "8") (pinfunction "PC0_8") (pintype "bidirectional"))
    )
    (net (code "62") (name "unconnected-(F1A-PC1-Pad9)") (class "Default")
      (node (ref "F1") (pin "9") (pinfunction "PC1_9") (pintype "bidirectional"))
    )
    (net (code "63") (name "unconnected-(F1A-PC2-Pad10)") (class "Default")
      (node (ref "F1") (pin "10") (pinfunction "PC2_10") (pintype "bidirectional"))
    )
    (net (code "64") (name "unconnected-(F1A-PC3-Pad11)") (class "Default")
      (node (ref "F1") (pin "11") (pinfunction "PC3_11") (pintype "bidirectional"))
    )
    (net (code "65") (name "unconnected-(F1A-PC4-Pad24)") (class "Default")
      (node (ref "F1") (pin "24") (pinfunction "PC4_24") (pintype "bidirectional"))
    )
    (net (code "66") (name "unconnected-(F1A-PC5-Pad25)") (class "Default")
      (node (ref "F1") (pin "25") (pinfunction "PC5_25") (pintype "bidirectional"))
    )
    (net (code "67") (name "unconnected-(F1A-PC6-Pad37)") (class "Default")
      (node (ref "F1") (pin "37") (pinfunction "PC6_37") (pintype "bidirectional"))
    )
    (net (code "68") (name "unconnected-(F1A-PC7-Pad38)") (class "Default")
      (node (ref "F1") (pin "38") (pinfunction "PC7_38") (pintype "bidirectional"))
    )
    (net (code "69") (name "unconnected-(F1A-PC8-Pad39)") (class "Default")
      (node (ref "F1") (pin "39") (pinfunction "PC8_39") (pintype "bidirectional"))
    )
    (net (code "70") (name "unconnected-(F1A-PC9-Pad40)") (class "Default")
      (node (ref "F1") (pin "40") (pinfunction "PC9_40") (pintype "bidirectional"))
    )
    (net (code "71") (name "unconnected-(F1A-PC10-Pad51)") (class "Default")
      (node (ref "F1") (pin "51") (pinfunction "PC10_51") (pintype "bidirectional"))
    )
    (net (code "72") (name "unconnected-(F1A-PC11-Pad52)") (class "Default")
      (node (ref "F1") (pin "52") (pinfunction "PC11_52") (pintype "bidirectional"))
    )
    (net (code "73") (name "unconnected-(F1A-PC12-Pad53)") (class "Default")
      (node (ref "F1") (pin "53") (pinfunction "PC12_53") (pintype "bidirectional"))
    )
    (net (code "74") (name "unconnected-(F1A-PC13-Pad2)") (class "Default")
      (node (ref "F1") (pin "2") (pinfunction "PC13_2") (pintype "bidirectional"))
    )
    (net (code "75") (name "unconnected-(F1A-PD2-Pad54)") (class "Default")
      (node (ref "F1") (pin "54") (pinfunction "PD2_54") (pintype "bidirectional"))
    )
    (net (code "76") (name "unconnected-(F3-I{slash}O1-Pad1)") (class "Default")
      (node (ref "F3") (pin "1") (pinfunction "I/O1_1") (pintype "passive"))
    )
    (net (code "77") (name "unconnected-(X2-SBU1-PadA8)") (class "Default")
      (node (ref "X2") (pin "A8") (pinfunction "SBU1_A8") (pintype "passive"))
    )
    (net (code "78") (name "unconnected-(X2-SBU2-PadB8)") (class "Default")
      (node (ref "X2") (pin "B8") (pinfunction "SBU2_B8") (pintype "bidirectional"))
    )
    (net (code "79") (name "unconnected-(X4-RTCK-Pad7)") (class "Default")
      (node (ref "X4") (pin "7") (pinfunction "RTCK_7") (pintype "power_in"))
    )
  )
)
